# TMUX130.net
KiCad netlist of a schematic drawn in Altium Designer
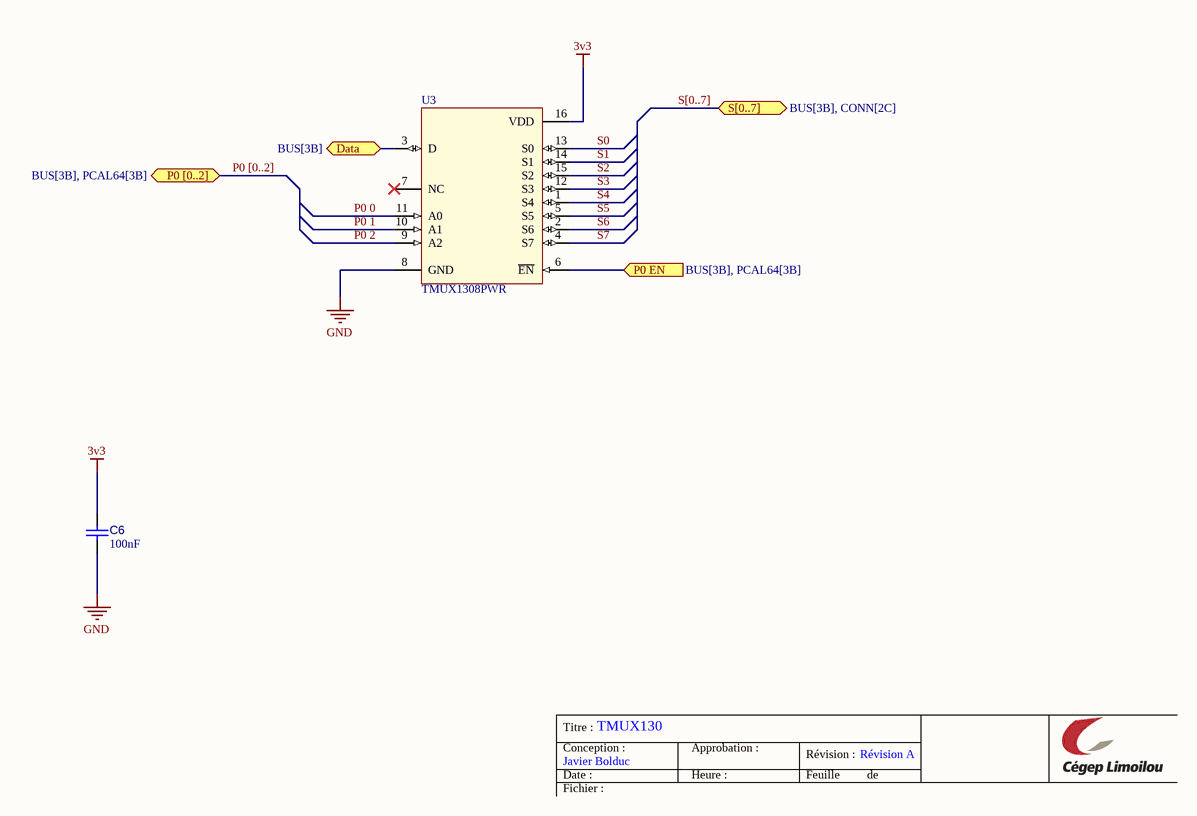
[diagram p0: TMUX130.schdoc]

(export (version "E")
  (design (tool "Eeschema 10.0.6"))
  (components
    (comp (ref "C6")
      (value "100nF")
      (footprint "C_1608[0603]")
      (description "Capacitor type 1")
      (fields (field (name "TOLERANCE") "10%") (field (name "Comment") "CAP CER 100nF 50V 0603"))
      (libsource (lib "TEP-AltiumLib-Passives-RLC") (part "capacitor"))
    )
    (comp (ref "U3")
      (value "TMUX1308PWR")
      (footprint "U_TSSOP65P500X450-16")
      (description "IC MUX 8:1 195OHM 16TSSOP")
      (libsource (lib "TEP-AltiumLib-ICs") (part "U_TMUX1308PWR"))
    )
  )
  (nets
    (net (code "1") (name "/Data") (class "Default")
      (node (ref "U3") (pin "3") (pinfunction "D_3") (pintype "bidirectional"))
    )
    (net (code "2") (name "/P0 0") (class "Default")
      (node (ref "U3") (pin "11") (pinfunction "A0_11") (pintype "input"))
    )
    (net (code "3") (name "/P0 1") (class "Default")
      (node (ref "U3") (pin "10") (pinfunction "A1_10") (pintype "input"))
    )
    (net (code "4") (name "/P0 2") (class "Default")
      (node (ref "U3") (pin "9") (pinfunction "A2_9") (pintype "input"))
    )
    (net (code "5") (name "/P0 EN") (class "Default")
      (node (ref "U3") (pin "6") (pinfunction "~{EN}_6") (pintype "input"))
    )
    (net (code "6") (name "/S0") (class "Default")
      (node (ref "U3") (pin "13") (pinfunction "S0_13") (pintype "bidirectional"))
    )
    (net (code "7") (name "/S1") (class "Default")
      (node (ref "U3") (pin "14") (pinfunction "S1_14") (pintype "bidirectional"))
    )
    (net (code "8") (name "/S2") (class "Default")
      (node (ref "U3") (pin "15") (pinfunction "S2_15") (pintype "bidirectional"))
    )
    (net (code "9") (name "/S3") (class "Default")
      (node (ref "U3") (pin "12") (pinfunction "S3_12") (pintype "bidirectional"))
    )
    (net (code "10") (name "/S4") (class "Default")
      (node (ref "U3") (pin "1") (pinfunction "S4_1") (pintype "bidirectional"))
    )
    (net (code "11") (name "/S5") (class "Default")
      (node (ref "U3") (pin "5") (pinfunction "S5_5") (pintype "bidirectional"))
    )
    (net (code "12") (name "/S6") (class "Default")
      (node (ref "U3") (pin "2") (pinfunction "S6_2") (pintype "bidirectional"))
    )
    (net (code "13") (name "/S7") (class "Default")
      (node (ref "U3") (pin "4") (pinfunction "S7_4") (pintype "bidirectional"))
    )
    (net (code "16") (name "3v3") (class "Default")
      (node (ref "C6") (pin "2") (pinfunction "2_2") (pintype "passive"))
      (node (ref "U3") (pin "16") (pinfunction "VDD_16") (pintype "power_in"))
    )
    (net (code "17") (name "GND") (class "Default")
      (node (ref "C6") (pin "1") (pinfunction "1_1") (pintype "passive"))
      (node (ref "U3") (pin "8") (pinfunction "GND_8") (pintype "power_in"))
    )
    (net (code "18") (name "unconnected-(U3-NC-Pad7)") (class "Default")
      (node (ref "U3") (pin "7") (pinfunction "NC_7") (pintype "passive+no_connect"))
    )
  )
)
